# DelayLine.net
KiCad netlist of a schematic drawn in Altium Designer
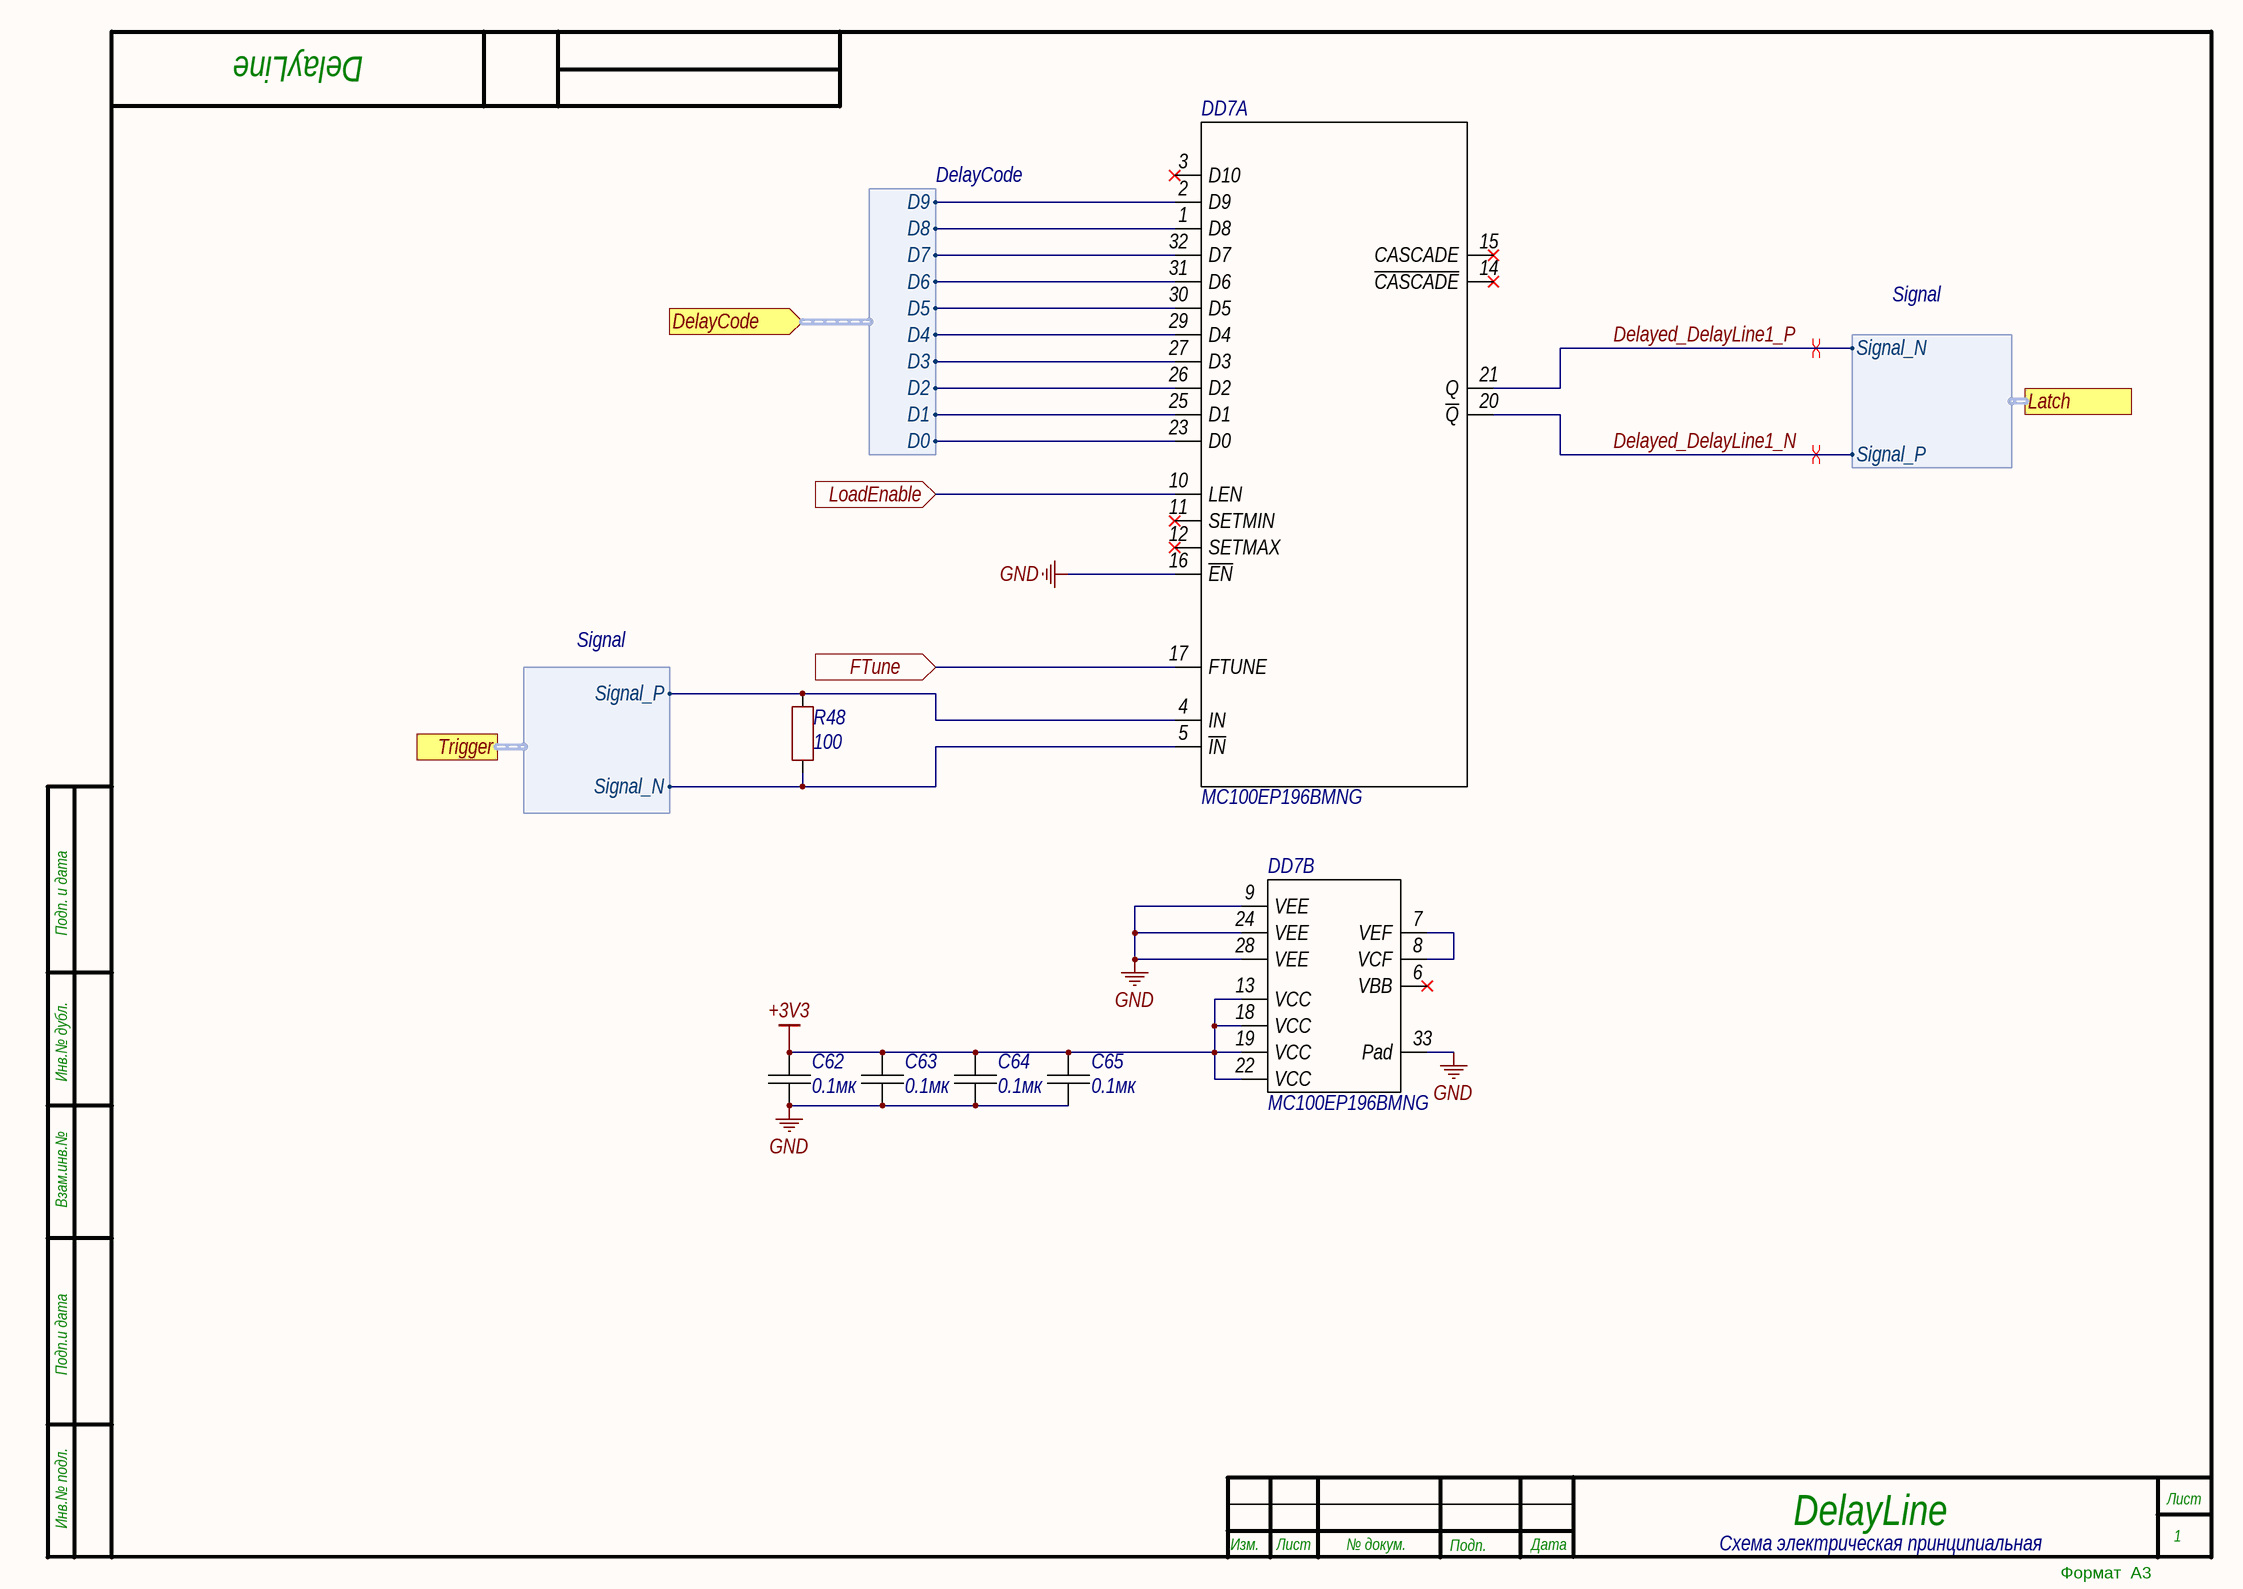
[diagram p0: DelayLine.SchDoc]

(export (version "E")
  (design (tool "Eeschema 10.0.6"))
  (components
    (comp (ref "C62")
      (value "0.1мк")
      (footprint "CAP0402")
      (fields (field (name "PART NUMBER") "CAP0402") (field (name "Comment") "0.1мк *"))
      (libsource (lib "Library") (part "CAPC"))
    )
    (comp (ref "C63")
      (value "0.1мк")
      (footprint "CAP0402")
      (fields (field (name "PART NUMBER") "CAP0402") (field (name "Comment") "0.1мк *"))
      (libsource (lib "Library") (part "CAPC"))
    )
    (comp (ref "C64")
      (value "0.1мк")
      (footprint "CAP0402")
      (fields (field (name "PART NUMBER") "CAP0402") (field (name "Comment") "0.1мк *"))
      (libsource (lib "Library") (part "CAPC"))
    )
    (comp (ref "C65")
      (value "0.1мк")
      (footprint "CAP0402")
      (fields (field (name "PART NUMBER") "CAP0402") (field (name "Comment") "0.1мк *"))
      (libsource (lib "Library") (part "CAPC"))
    )
    (comp (ref "DD7")
      (value "MC100EP196BMNG")
      (footprint "QFN-32_N_TP")
      (fields (field (name "MPN") "MC100EP196BMNG") (field (name "MANUFACTURER") "ONSEMI"))
      (libsource (lib "Library") (part "MC100EP196BMNG"))
    )
    (comp (ref "R48")
      (value "100")
      (footprint "RESC0402(1005)_M")
      (fields (field (name "PART NUMBER") "RES0402") (field (name "Comment") "100 "))
      (libsource (lib "Library") (part "RES"))
    )
  )
  (nets
    (net (code "3") (name "+3V3") (class "Default")
      (node (ref "C62") (pin "1") (pinfunction "1_1") (pintype "passive"))
      (node (ref "C63") (pin "1") (pinfunction "1_1") (pintype "passive"))
      (node (ref "C64") (pin "1") (pinfunction "1_1") (pintype "passive"))
      (node (ref "C65") (pin "1") (pinfunction "1_1") (pintype "passive"))
      (node (ref "DD7") (pin "13") (pinfunction "VCC_13") (pintype "passive"))
      (node (ref "DD7") (pin "18") (pinfunction "VCC_18") (pintype "passive"))
      (node (ref "DD7") (pin "19") (pinfunction "VCC_19") (pintype "passive"))
      (node (ref "DD7") (pin "22") (pinfunction "VCC_22") (pintype "passive"))
    )
    (net (code "4") (name "/D0") (class "Default")
      (node (ref "DD7") (pin "23") (pinfunction "D0_23") (pintype "passive"))
    )
    (net (code "5") (name "/D1") (class "Default")
      (node (ref "DD7") (pin "25") (pinfunction "D1_25") (pintype "passive"))
    )
    (net (code "6") (name "/D2") (class "Default")
      (node (ref "DD7") (pin "26") (pinfunction "D2_26") (pintype "passive"))
    )
    (net (code "7") (name "/D3") (class "Default")
      (node (ref "DD7") (pin "27") (pinfunction "D3_27") (pintype "passive"))
    )
    (net (code "8") (name "/D4") (class "Default")
      (node (ref "DD7") (pin "29") (pinfunction "D4_29") (pintype "passive"))
    )
    (net (code "9") (name "/D5") (class "Default")
      (node (ref "DD7") (pin "30") (pinfunction "D5_30") (pintype "passive"))
    )
    (net (code "10") (name "/D6") (class "Default")
      (node (ref "DD7") (pin "31") (pinfunction "D6_31") (pintype "passive"))
    )
    (net (code "11") (name "/D7") (class "Default")
      (node (ref "DD7") (pin "32") (pinfunction "D7_32") (pintype "passive"))
    )
    (net (code "12") (name "/D8") (class "Default")
      (node (ref "DD7") (pin "1") (pinfunction "D8_1") (pintype "passive"))
    )
    (net (code "13") (name "/D9") (class "Default")
      (node (ref "DD7") (pin "2") (pinfunction "D9_2") (pintype "passive"))
    )
    (net (code "14") (name "/Delayed_DelayLine1_N") (class "Default")
      (node (ref "DD7") (pin "20") (pinfunction "~{Q}_20") (pintype "passive"))
    )
    (net (code "15") (name "/Delayed_DelayLine1_P") (class "Default")
      (node (ref "DD7") (pin "21") (pinfunction "Q_21") (pintype "passive"))
    )
    (net (code "16") (name "/FTune") (class "Default")
      (node (ref "DD7") (pin "17") (pinfunction "FTUNE_17") (pintype "passive"))
    )
    (net (code "17") (name "/LoadEnable") (class "Default")
      (node (ref "DD7") (pin "10") (pinfunction "LEN_10") (pintype "passive"))
    )
    (net (code "20") (name "GND") (class "Default")
      (node (ref "C62") (pin "2") (pinfunction "2_2") (pintype "passive"))
      (node (ref "C63") (pin "2") (pinfunction "2_2") (pintype "passive"))
      (node (ref "C64") (pin "2") (pinfunction "2_2") (pintype "passive"))
      (node (ref "C65") (pin "2") (pinfunction "2_2") (pintype "passive"))
      (node (ref "DD7") (pin "16") (pinfunction "~{EN}_16") (pintype "passive"))
      (node (ref "DD7") (pin "24") (pinfunction "VEE_24") (pintype "passive"))
      (node (ref "DD7") (pin "28") (pinfunction "VEE_28") (pintype "passive"))
      (node (ref "DD7") (pin "33") (pinfunction "Pad_33") (pintype "passive"))
      (node (ref "DD7") (pin "9") (pinfunction "VEE_9") (pintype "passive"))
    )
    (net (code "21") (name "Net-(DD7A-IN)") (class "Default")
      (node (ref "DD7") (pin "4") (pinfunction "IN_4") (pintype "passive"))
      (node (ref "R48") (pin "2") (pinfunction "2_2") (pintype "passive"))
    )
    (net (code "22") (name "Net-(DD7A-~{IN})") (class "Default")
      (node (ref "DD7") (pin "5") (pinfunction "~{IN}_5") (pintype "passive"))
      (node (ref "R48") (pin "1") (pinfunction "1_1") (pintype "passive"))
    )
    (net (code "23") (name "Net-(DD7B-VCF)") (class "Default")
      (node (ref "DD7") (pin "7") (pinfunction "VEF_7") (pintype "passive"))
      (node (ref "DD7") (pin "8") (pinfunction "VCF_8") (pintype "passive"))
    )
    (net (code "24") (name "unconnected-(DD7A-CASCADE-Pad15)") (class "Default")
      (node (ref "DD7") (pin "15") (pinfunction "CASCADE_15") (pintype "passive+no_connect"))
    )
    (net (code "25") (name "unconnected-(DD7A-D10-Pad3)") (class "Default")
      (node (ref "DD7") (pin "3") (pinfunction "D10_3") (pintype "passive+no_connect"))
    )
    (net (code "26") (name "unconnected-(DD7A-SETMAX-Pad12)") (class "Default")
      (node (ref "DD7") (pin "12") (pinfunction "SETMAX_12") (pintype "passive+no_connect"))
    )
    (net (code "27") (name "unconnected-(DD7A-SETMIN-Pad11)") (class "Default")
      (node (ref "DD7") (pin "11") (pinfunction "SETMIN_11") (pintype "passive+no_connect"))
    )
    (net (code "28") (name "unconnected-(DD7A-~{CASCADE}-Pad14)") (class "Default")
      (node (ref "DD7") (pin "14") (pinfunction "~{CASCADE}_14") (pintype "passive+no_connect"))
    )
    (net (code "29") (name "unconnected-(DD7B-VBB-Pad6)") (class "Default")
      (node (ref "DD7") (pin "6") (pinfunction "VBB_6") (pintype "passive+no_connect"))
    )
  )
)
